# PWM_QSPI_SPI_ADC_UART_GPIO_I2C.net
KiCad netlist of a schematic drawn in Altium Designer
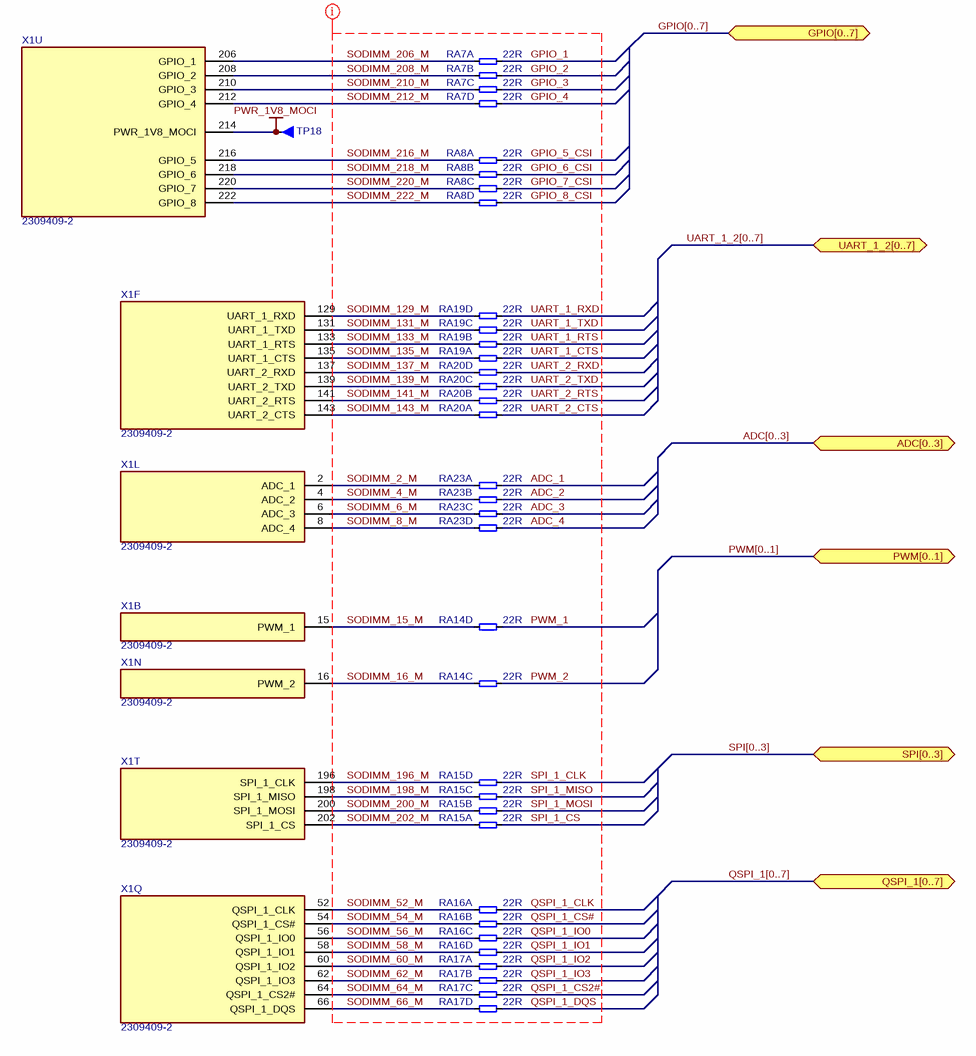
[diagram p0: PWM_QSPI_SPI_ADC_UART_GPIO_I2C.SchDoc]

(export (version "E")
  (design (tool "Eeschema 10.0.6"))
  (components
    (comp (ref "RA7")
      (value "22R")
      (footprint "T_Resistor_Array_X4")
      (description "Resistor Array 22 R 63mW 5% 1206")
      (fields (field (name "TOLERANCE") "5%"))
      (libsource (lib "Dahlia Carrier Board") (part "RA-22R-63mW-5%-1206-div"))
    )
    (comp (ref "RA8")
      (value "22R")
      (footprint "T_Resistor_Array_X4")
      (description "Resistor Array 22 R 63mW 5% 1206")
      (fields (field (name "TOLERANCE") "5%"))
      (libsource (lib "Dahlia Carrier Board") (part "RA-22R-63mW-5%-1206-div"))
    )
    (comp (ref "RA14")
      (value "22R")
      (footprint "T_Resistor_Array_X4")
      (description "Resistor Array 22 R 63mW 5% 1206")
      (fields (field (name "TOLERANCE") "5%"))
      (libsource (lib "Dahlia Carrier Board") (part "RA-22R-63mW-5%-1206-div"))
    )
    (comp (ref "RA15")
      (value "22R")
      (footprint "T_Resistor_Array_X4")
      (description "Resistor Array 22 R 63mW 5% 1206")
      (fields (field (name "TOLERANCE") "5%"))
      (libsource (lib "Dahlia Carrier Board") (part "RA-22R-63mW-5%-1206-div"))
    )
    (comp (ref "RA16")
      (value "22R")
      (footprint "T_Resistor_Array_X4")
      (description "Resistor Array 22 R 63mW 5% 1206")
      (fields (field (name "TOLERANCE") "5%"))
      (libsource (lib "Dahlia Carrier Board") (part "RA-22R-63mW-5%-1206-div"))
    )
    (comp (ref "RA17")
      (value "22R")
      (footprint "T_Resistor_Array_X4")
      (description "Resistor Array 22 R 63mW 5% 1206")
      (fields (field (name "TOLERANCE") "5%"))
      (libsource (lib "Dahlia Carrier Board") (part "RA-22R-63mW-5%-1206-div"))
    )
    (comp (ref "RA19")
      (value "22R")
      (footprint "T_Resistor_Array_X4")
      (description "Resistor Array 22 R 63mW 5% 1206")
      (fields (field (name "TOLERANCE") "5%"))
      (libsource (lib "Dahlia Carrier Board") (part "RA-22R-63mW-5%-1206-div"))
    )
    (comp (ref "RA20")
      (value "22R")
      (footprint "T_Resistor_Array_X4")
      (description "Resistor Array 22 R 63mW 5% 1206")
      (fields (field (name "TOLERANCE") "5%"))
      (libsource (lib "Dahlia Carrier Board") (part "RA-22R-63mW-5%-1206-div"))
    )
    (comp (ref "RA23")
      (value "22R")
      (footprint "T_Resistor_Array_X4")
      (description "Resistor Array 22 R 63mW 5% 1206")
      (fields (field (name "TOLERANCE") "5%"))
      (libsource (lib "Dahlia Carrier Board") (part "RA-22R-63mW-5%-1206-div"))
    )
    (comp (ref "TP18")
      (value "Testpin-THT")
      (footprint "T_TP-THT")
      (description "Testpin THT")
      (libsource (lib "Dahlia Carrier Board") (part "Testpin-THT"))
    )
    (comp (ref "X1")
      (value "2309409-2")
      (footprint "CON-TE-2309409-2-SOLDERABLE-STANDOFFS")
      (description "DDR4 SODIMM Socket, 260 pins, 5.2mm(H), 0.5mm Pitch")
      (libsource (lib "Dahlia Carrier Board") (part "CON-TE-2309409-2"))
    )
  )
  (nets
    (net (code "36") (name "/ADC_1") (class "Default")
      (node (ref "RA23") (pin "5") (pinfunction "5_5") (pintype "passive"))
    )
    (net (code "37") (name "/ADC_2") (class "Default")
      (node (ref "RA23") (pin "6") (pinfunction "6_6") (pintype "passive"))
    )
    (net (code "38") (name "/ADC_3") (class "Default")
      (node (ref "RA23") (pin "7") (pinfunction "7_7") (pintype "passive"))
    )
    (net (code "39") (name "/ADC_4") (class "Default")
      (node (ref "RA23") (pin "8") (pinfunction "8_8") (pintype "passive"))
    )
    (net (code "41") (name "/GPIO_1") (class "Default")
      (node (ref "RA7") (pin "5") (pinfunction "5_5") (pintype "passive"))
    )
    (net (code "42") (name "/GPIO_2") (class "Default")
      (node (ref "RA7") (pin "6") (pinfunction "6_6") (pintype "passive"))
    )
    (net (code "43") (name "/GPIO_3") (class "Default")
      (node (ref "RA7") (pin "7") (pinfunction "7_7") (pintype "passive"))
    )
    (net (code "44") (name "/GPIO_4") (class "Default")
      (node (ref "RA7") (pin "8") (pinfunction "8_8") (pintype "passive"))
    )
    (net (code "45") (name "/GPIO_5_CSI") (class "Default")
      (node (ref "RA8") (pin "5") (pinfunction "5_5") (pintype "passive"))
    )
    (net (code "46") (name "/GPIO_6_CSI") (class "Default")
      (node (ref "RA8") (pin "6") (pinfunction "6_6") (pintype "passive"))
    )
    (net (code "47") (name "/GPIO_7_CSI") (class "Default")
      (node (ref "RA8") (pin "7") (pinfunction "7_7") (pintype "passive"))
    )
    (net (code "48") (name "/GPIO_8_CSI") (class "Default")
      (node (ref "RA8") (pin "8") (pinfunction "8_8") (pintype "passive"))
    )
    (net (code "50") (name "/PWM_1") (class "Default")
      (node (ref "RA14") (pin "8") (pinfunction "8_8") (pintype "passive"))
    )
    (net (code "51") (name "/PWM_2") (class "Default")
      (node (ref "RA14") (pin "7") (pinfunction "7_7") (pintype "passive"))
    )
    (net (code "53") (name "/QSPI_1_CLK") (class "Default")
      (node (ref "RA16") (pin "5") (pinfunction "5_5") (pintype "passive"))
    )
    (net (code "54") (name "/QSPI_1_CS#") (class "Default")
      (node (ref "RA16") (pin "6") (pinfunction "6_6") (pintype "passive"))
    )
    (net (code "55") (name "/QSPI_1_CS2#") (class "Default")
      (node (ref "RA17") (pin "7") (pinfunction "7_7") (pintype "passive"))
    )
    (net (code "56") (name "/QSPI_1_DQS") (class "Default")
      (node (ref "RA17") (pin "8") (pinfunction "8_8") (pintype "passive"))
    )
    (net (code "57") (name "/QSPI_1_IO0") (class "Default")
      (node (ref "RA16") (pin "7") (pinfunction "7_7") (pintype "passive"))
    )
    (net (code "58") (name "/QSPI_1_IO1") (class "Default")
      (node (ref "RA16") (pin "8") (pinfunction "8_8") (pintype "passive"))
    )
    (net (code "59") (name "/QSPI_1_IO2") (class "Default")
      (node (ref "RA17") (pin "5") (pinfunction "5_5") (pintype "passive"))
    )
    (net (code "60") (name "/QSPI_1_IO3") (class "Default")
      (node (ref "RA17") (pin "6") (pinfunction "6_6") (pintype "passive"))
    )
    (net (code "61") (name "/SODIMM_2_M") (class "Default")
      (node (ref "RA23") (pin "1") (pinfunction "1_1") (pintype "passive"))
      (node (ref "X1") (pin "2") (pinfunction "ADC_1_2") (pintype "passive"))
    )
    (net (code "62") (name "/SODIMM_4_M") (class "Default")
      (node (ref "RA23") (pin "2") (pinfunction "2_2") (pintype "passive"))
      (node (ref "X1") (pin "4") (pinfunction "ADC_2_4") (pintype "passive"))
    )
    (net (code "63") (name "/SODIMM_6_M") (class "Default")
      (node (ref "RA23") (pin "3") (pinfunction "3_3") (pintype "passive"))
      (node (ref "X1") (pin "6") (pinfunction "ADC_3_6") (pintype "passive"))
    )
    (net (code "64") (name "/SODIMM_8_M") (class "Default")
      (node (ref "RA23") (pin "4") (pinfunction "4_4") (pintype "passive"))
      (node (ref "X1") (pin "8") (pinfunction "ADC_4_8") (pintype "passive"))
    )
    (net (code "65") (name "/SODIMM_15_M") (class "Default")
      (node (ref "RA14") (pin "4") (pinfunction "4_4") (pintype "passive"))
      (node (ref "X1") (pin "15") (pinfunction "PWM_1_15") (pintype "passive"))
    )
    (net (code "66") (name "/SODIMM_16_M") (class "Default")
      (node (ref "RA14") (pin "3") (pinfunction "3_3") (pintype "passive"))
      (node (ref "X1") (pin "16") (pinfunction "PWM_2_16") (pintype "passive"))
    )
    (net (code "67") (name "/SODIMM_52_M") (class "Default")
      (node (ref "RA16") (pin "1") (pinfunction "1_1") (pintype "passive"))
      (node (ref "X1") (pin "52") (pinfunction "QSPI_1_CLK_52") (pintype "passive"))
    )
    (net (code "68") (name "/SODIMM_54_M") (class "Default")
      (node (ref "RA16") (pin "2") (pinfunction "2_2") (pintype "passive"))
      (node (ref "X1") (pin "54") (pinfunction "QSPI_1_CS#_54") (pintype "passive"))
    )
    (net (code "69") (name "/SODIMM_56_M") (class "Default")
      (node (ref "RA16") (pin "3") (pinfunction "3_3") (pintype "passive"))
      (node (ref "X1") (pin "56") (pinfunction "QSPI_1_IO0_56") (pintype "passive"))
    )
    (net (code "70") (name "/SODIMM_58_M") (class "Default")
      (node (ref "RA16") (pin "4") (pinfunction "4_4") (pintype "passive"))
      (node (ref "X1") (pin "58") (pinfunction "QSPI_1_IO1_58") (pintype "passive"))
    )
    (net (code "71") (name "/SODIMM_60_M") (class "Default")
      (node (ref "RA17") (pin "1") (pinfunction "1_1") (pintype "passive"))
      (node (ref "X1") (pin "60") (pinfunction "QSPI_1_IO2_60") (pintype "passive"))
    )
    (net (code "72") (name "/SODIMM_62_M") (class "Default")
      (node (ref "RA17") (pin "2") (pinfunction "2_2") (pintype "passive"))
      (node (ref "X1") (pin "62") (pinfunction "QSPI_1_IO3_62") (pintype "passive"))
    )
    (net (code "73") (name "/SODIMM_64_M") (class "Default")
      (node (ref "RA17") (pin "3") (pinfunction "3_3") (pintype "passive"))
      (node (ref "X1") (pin "64") (pinfunction "QSPI_1_CS2#_64") (pintype "passive"))
    )
    (net (code "74") (name "/SODIMM_66_M") (class "Default")
      (node (ref "RA17") (pin "4") (pinfunction "4_4") (pintype "passive"))
      (node (ref "X1") (pin "66") (pinfunction "QSPI_1_DQS_66") (pintype "passive"))
    )
    (net (code "75") (name "/SODIMM_129_M") (class "Default")
      (node (ref "RA19") (pin "4") (pinfunction "4_4") (pintype "passive"))
      (node (ref "X1") (pin "129") (pinfunction "UART_1_RXD_129") (pintype "passive"))
    )
    (net (code "76") (name "/SODIMM_131_M") (class "Default")
      (node (ref "RA19") (pin "3") (pinfunction "3_3") (pintype "passive"))
      (node (ref "X1") (pin "131") (pinfunction "UART_1_TXD_131") (pintype "passive"))
    )
    (net (code "77") (name "/SODIMM_133_M") (class "Default")
      (node (ref "RA19") (pin "2") (pinfunction "2_2") (pintype "passive"))
      (node (ref "X1") (pin "133") (pinfunction "UART_1_RTS_133") (pintype "passive"))
    )
    (net (code "78") (name "/SODIMM_135_M") (class "Default")
      (node (ref "RA19") (pin "1") (pinfunction "1_1") (pintype "passive"))
      (node (ref "X1") (pin "135") (pinfunction "UART_1_CTS_135") (pintype "passive"))
    )
    (net (code "79") (name "/SODIMM_137_M") (class "Default")
      (node (ref "RA20") (pin "4") (pinfunction "4_4") (pintype "passive"))
      (node (ref "X1") (pin "137") (pinfunction "UART_2_RXD_137") (pintype "passive"))
    )
    (net (code "80") (name "/SODIMM_139_M") (class "Default")
      (node (ref "RA20") (pin "3") (pinfunction "3_3") (pintype "passive"))
      (node (ref "X1") (pin "139") (pinfunction "UART_2_TXD_139") (pintype "passive"))
    )
    (net (code "81") (name "/SODIMM_141_M") (class "Default")
      (node (ref "RA20") (pin "2") (pinfunction "2_2") (pintype "passive"))
      (node (ref "X1") (pin "141") (pinfunction "UART_2_RTS_141") (pintype "passive"))
    )
    (net (code "82") (name "/SODIMM_143_M") (class "Default")
      (node (ref "RA20") (pin "1") (pinfunction "1_1") (pintype "passive"))
      (node (ref "X1") (pin "143") (pinfunction "UART_2_CTS_143") (pintype "passive"))
    )
    (net (code "83") (name "/SODIMM_196_M") (class "Default")
      (node (ref "RA15") (pin "4") (pinfunction "4_4") (pintype "passive"))
      (node (ref "X1") (pin "196") (pinfunction "SPI_1_CLK_196") (pintype "passive"))
    )
    (net (code "84") (name "/SODIMM_198_M") (class "Default")
      (node (ref "RA15") (pin "3") (pinfunction "3_3") (pintype "passive"))
      (node (ref "X1") (pin "198") (pinfunction "SPI_1_MISO_198") (pintype "passive"))
    )
    (net (code "85") (name "/SODIMM_200_M") (class "Default")
      (node (ref "RA15") (pin "2") (pinfunction "2_2") (pintype "passive"))
      (node (ref "X1") (pin "200") (pinfunction "SPI_1_MOSI_200") (pintype "passive"))
    )
    (net (code "86") (name "/SODIMM_202_M") (class "Default")
      (node (ref "RA15") (pin "1") (pinfunction "1_1") (pintype "passive"))
      (node (ref "X1") (pin "202") (pinfunction "SPI_1_CS_202") (pintype "passive"))
    )
    (net (code "87") (name "/SODIMM_206_M") (class "Default")
      (node (ref "RA7") (pin "1") (pinfunction "1_1") (pintype "passive"))
      (node (ref "X1") (pin "206") (pinfunction "GPIO_1_206") (pintype "passive"))
    )
    (net (code "88") (name "/SODIMM_208_M") (class "Default")
      (node (ref "RA7") (pin "2") (pinfunction "2_2") (pintype "passive"))
      (node (ref "X1") (pin "208") (pinfunction "GPIO_2_208") (pintype "passive"))
    )
    (net (code "89") (name "/SODIMM_210_M") (class "Default")
      (node (ref "RA7") (pin "3") (pinfunction "3_3") (pintype "passive"))
      (node (ref "X1") (pin "210") (pinfunction "GPIO_3_210") (pintype "passive"))
    )
    (net (code "90") (name "/SODIMM_212_M") (class "Default")
      (node (ref "RA7") (pin "4") (pinfunction "4_4") (pintype "passive"))
      (node (ref "X1") (pin "212") (pinfunction "GPIO_4_212") (pintype "passive"))
    )
    (net (code "91") (name "/SODIMM_216_M") (class "Default")
      (node (ref "RA8") (pin "1") (pinfunction "1_1") (pintype "passive"))
      (node (ref "X1") (pin "216") (pinfunction "GPIO_5_216") (pintype "passive"))
    )
    (net (code "92") (name "/SODIMM_218_M") (class "Default")
      (node (ref "RA8") (pin "2") (pinfunction "2_2") (pintype "passive"))
      (node (ref "X1") (pin "218") (pinfunction "GPIO_6_218") (pintype "passive"))
    )
    (net (code "93") (name "/SODIMM_220_M") (class "Default")
      (node (ref "RA8") (pin "3") (pinfunction "3_3") (pintype "passive"))
      (node (ref "X1") (pin "220") (pinfunction "GPIO_7_220") (pintype "passive"))
    )
    (net (code "94") (name "/SODIMM_222_M") (class "Default")
      (node (ref "RA8") (pin "4") (pinfunction "4_4") (pintype "passive"))
      (node (ref "X1") (pin "222") (pinfunction "GPIO_8_222") (pintype "passive"))
    )
    (net (code "96") (name "/SPI_1_CLK") (class "Default")
      (node (ref "RA15") (pin "8") (pinfunction "8_8") (pintype "passive"))
    )
    (net (code "97") (name "/SPI_1_CS") (class "Default")
      (node (ref "RA15") (pin "5") (pinfunction "5_5") (pintype "passive"))
    )
    (net (code "98") (name "/SPI_1_MISO") (class "Default")
      (node (ref "RA15") (pin "7") (pinfunction "7_7") (pintype "passive"))
    )
    (net (code "99") (name "/SPI_1_MOSI") (class "Default")
      (node (ref "RA15") (pin "6") (pinfunction "6_6") (pintype "passive"))
    )
    (net (code "101") (name "/UART_1_CTS") (class "Default")
      (node (ref "RA19") (pin "5") (pinfunction "5_5") (pintype "passive"))
    )
    (net (code "102") (name "/UART_1_RTS") (class "Default")
      (node (ref "RA19") (pin "6") (pinfunction "6_6") (pintype "passive"))
    )
    (net (code "103") (name "/UART_1_RXD") (class "Default")
      (node (ref "RA19") (pin "8") (pinfunction "8_8") (pintype "passive"))
    )
    (net (code "104") (name "/UART_1_TXD") (class "Default")
      (node (ref "RA19") (pin "7") (pinfunction "7_7") (pintype "passive"))
    )
    (net (code "105") (name "/UART_2_CTS") (class "Default")
      (node (ref "RA20") (pin "5") (pinfunction "5_5") (pintype "passive"))
    )
    (net (code "106") (name "/UART_2_RTS") (class "Default")
      (node (ref "RA20") (pin "6") (pinfunction "6_6") (pintype "passive"))
    )
    (net (code "107") (name "/UART_2_RXD") (class "Default")
      (node (ref "RA20") (pin "8") (pinfunction "8_8") (pintype "passive"))
    )
    (net (code "108") (name "/UART_2_TXD") (class "Default")
      (node (ref "RA20") (pin "7") (pinfunction "7_7") (pintype "passive"))
    )
    (net (code "109") (name "PWR_1V8_MOCI") (class "Default")
      (node (ref "TP18") (pin "1") (pinfunction "1_1") (pintype "passive"))
      (node (ref "X1") (pin "214") (pinfunction "PWR_1V8_MOCI_214") (pintype "passive"))
    )
  )
)
